# pcbcsmd.net
KiCad netlist of a schematic drawn in EAGLE
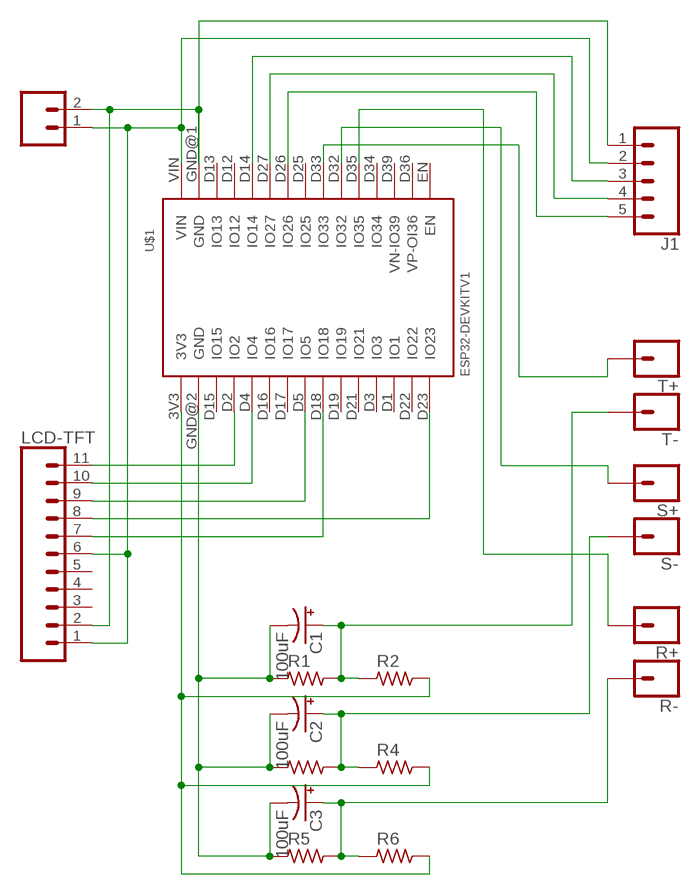
[diagram p0: schematic, sheet 1]

(export (version "E")
  (design (tool "Eeschema 10.0.6"))
  (components
    (comp (ref "C1")
      (value "100uF")
      (footprint "eagle-import:PANASONIC_D")
      (libsource (lib "eagle-import") (part "100UF-POLAR-25V-20%(ELEC)"))
    )
    (comp (ref "C2")
      (value "100uF")
      (footprint "eagle-import:PANASONIC_D")
      (libsource (lib "eagle-import") (part "100UF-POLAR-25V-20%(ELEC)"))
    )
    (comp (ref "C3")
      (value "100uF")
      (footprint "eagle-import:PANASONIC_D")
      (libsource (lib "eagle-import") (part "100UF-POLAR-25V-20%(ELEC)"))
    )
    (comp (ref "J1")
      (value "CONN_05")
      (footprint "eagle-import:1X05")
      (libsource (lib "eagle-import") (part "CONN_05"))
    )
    (comp (ref "LCD-TFT")
      (value "CONN_11")
      (footprint "eagle-import:1X11")
      (libsource (lib "eagle-import") (part "CONN_11"))
    )
    (comp (ref "POWER")
      (value "CONN_02")
      (footprint "eagle-import:1X02")
      (libsource (lib "eagle-import") (part "CONN_02"))
    )
    (comp (ref "R+")
      (value "CONN_01")
      (footprint "eagle-import:1X01")
      (libsource (lib "eagle-import") (part "CONN_01"))
    )
    (comp (ref "R-")
      (value "CONN_01")
      (footprint "eagle-import:1X01")
      (libsource (lib "eagle-import") (part "CONN_01"))
    )
    (comp (ref "R1")
      (value "R_0805")
      (footprint "eagle-import:R0805")
      (libsource (lib "eagle-import") (part "R_0805"))
    )
    (comp (ref "R2")
      (value "R_0805")
      (footprint "eagle-import:R0805")
      (libsource (lib "eagle-import") (part "R_0805"))
    )
    (comp (ref "R3")
      (value "R_0805")
      (footprint "eagle-import:R0805")
      (libsource (lib "eagle-import") (part "R_0805"))
    )
    (comp (ref "R4")
      (value "R_0805")
      (footprint "eagle-import:R0805")
      (libsource (lib "eagle-import") (part "R_0805"))
    )
    (comp (ref "R5")
      (value "R_0805")
      (footprint "eagle-import:R0805")
      (libsource (lib "eagle-import") (part "R_0805"))
    )
    (comp (ref "R6")
      (value "R_0805")
      (footprint "eagle-import:R0805")
      (libsource (lib "eagle-import") (part "R_0805"))
    )
    (comp (ref "S+")
      (value "CONN_01")
      (footprint "eagle-import:1X01")
      (libsource (lib "eagle-import") (part "CONN_01"))
    )
    (comp (ref "S-")
      (value "CONN_01")
      (footprint "eagle-import:1X01")
      (libsource (lib "eagle-import") (part "CONN_01"))
    )
    (comp (ref "T+")
      (value "CONN_01")
      (footprint "eagle-import:1X01")
      (libsource (lib "eagle-import") (part "CONN_01"))
    )
    (comp (ref "T-")
      (value "CONN_01")
      (footprint "eagle-import:1X01")
      (libsource (lib "eagle-import") (part "CONN_01"))
    )
    (comp (ref "U$1")
      (value "ESP32DEVKITV1")
      (footprint "eagle-import:ESP32-DEVKITV1")
      (libsource (lib "eagle-import") (part "ESP32DEVKITV1"))
    )
  )
  (nets
    (net (code "1") (name "Net-(C1-Pad+)") (class "Default")
      (node (ref "C1") (pin "+") (pinfunction "+_+") (pintype "passive"))
      (node (ref "R1") (pin "2") (pinfunction "2_2") (pintype "passive"))
      (node (ref "R2") (pin "1") (pinfunction "1_1") (pintype "passive"))
      (node (ref "T-") (pin "1") (pinfunction "1_1") (pintype "passive"))
    )
    (net (code "2") (name "Net-(C1-Pad-)") (class "Default")
      (node (ref "C1") (pin "-") (pinfunction "-_-") (pintype "passive"))
      (node (ref "C2") (pin "-") (pinfunction "-_-") (pintype "passive"))
      (node (ref "C3") (pin "-") (pinfunction "-_-") (pintype "passive"))
      (node (ref "R1") (pin "1") (pinfunction "1_1") (pintype "passive"))
      (node (ref "R3") (pin "1") (pinfunction "1_1") (pintype "passive"))
      (node (ref "R5") (pin "1") (pinfunction "1_1") (pintype "passive"))
      (node (ref "U$1") (pin "GND@2") (pinfunction "GND_GND@2") (pintype "bidirectional"))
    )
    (net (code "3") (name "Net-(C2-Pad+)") (class "Default")
      (node (ref "C2") (pin "+") (pinfunction "+_+") (pintype "passive"))
      (node (ref "R3") (pin "2") (pinfunction "2_2") (pintype "passive"))
      (node (ref "R4") (pin "1") (pinfunction "1_1") (pintype "passive"))
      (node (ref "S-") (pin "1") (pinfunction "1_1") (pintype "passive"))
    )
    (net (code "4") (name "Net-(C3-Pad+)") (class "Default")
      (node (ref "C3") (pin "+") (pinfunction "+_+") (pintype "passive"))
      (node (ref "R-") (pin "1") (pinfunction "1_1") (pintype "passive"))
      (node (ref "R5") (pin "2") (pinfunction "2_2") (pintype "passive"))
      (node (ref "R6") (pin "1") (pinfunction "1_1") (pintype "passive"))
    )
    (net (code "5") (name "Net-(J1-Pad1)") (class "Default")
      (node (ref "J1") (pin "1") (pinfunction "1_1") (pintype "passive"))
      (node (ref "LCD-TFT") (pin "2") (pinfunction "2_2") (pintype "passive"))
      (node (ref "POWER") (pin "2") (pinfunction "2_2") (pintype "passive"))
      (node (ref "U$1") (pin "GND@1") (pinfunction "GND_GND@1") (pintype "bidirectional"))
    )
    (net (code "6") (name "Net-(J1-Pad2)") (class "Default")
      (node (ref "J1") (pin "2") (pinfunction "2_2") (pintype "passive"))
      (node (ref "LCD-TFT") (pin "1") (pinfunction "1_1") (pintype "passive"))
      (node (ref "LCD-TFT") (pin "6") (pinfunction "6_6") (pintype "passive"))
      (node (ref "POWER") (pin "1") (pinfunction "1_1") (pintype "passive"))
      (node (ref "U$1") (pin "VIN") (pinfunction "VIN_VIN") (pintype "bidirectional"))
    )
    (net (code "7") (name "Net-(R2-Pad2)") (class "Default")
      (node (ref "R2") (pin "2") (pinfunction "2_2") (pintype "passive"))
      (node (ref "R4") (pin "2") (pinfunction "2_2") (pintype "passive"))
      (node (ref "R6") (pin "2") (pinfunction "2_2") (pintype "passive"))
      (node (ref "U$1") (pin "3V3") (pinfunction "3V3_3V3") (pintype "bidirectional"))
    )
    (net (code "8") (name "Net-(U$1-IO2)") (class "Default")
      (node (ref "LCD-TFT") (pin "11") (pinfunction "11_11") (pintype "passive"))
      (node (ref "U$1") (pin "D2") (pinfunction "IO2_D2") (pintype "bidirectional"))
    )
    (net (code "9") (name "Net-(U$1-IO4)") (class "Default")
      (node (ref "LCD-TFT") (pin "10") (pinfunction "10_10") (pintype "passive"))
      (node (ref "U$1") (pin "D4") (pinfunction "IO4_D4") (pintype "bidirectional"))
    )
    (net (code "10") (name "Net-(U$1-IO5)") (class "Default")
      (node (ref "LCD-TFT") (pin "9") (pinfunction "9_9") (pintype "passive"))
      (node (ref "U$1") (pin "D5") (pinfunction "IO5_D5") (pintype "bidirectional"))
    )
    (net (code "11") (name "Net-(U$1-IO14)") (class "Default")
      (node (ref "J1") (pin "3") (pinfunction "3_3") (pintype "passive"))
      (node (ref "U$1") (pin "D14") (pinfunction "IO14_D14") (pintype "bidirectional"))
    )
    (net (code "12") (name "Net-(U$1-IO18)") (class "Default")
      (node (ref "LCD-TFT") (pin "7") (pinfunction "7_7") (pintype "passive"))
      (node (ref "U$1") (pin "D18") (pinfunction "IO18_D18") (pintype "bidirectional"))
    )
    (net (code "13") (name "Net-(U$1-IO23)") (class "Default")
      (node (ref "LCD-TFT") (pin "8") (pinfunction "8_8") (pintype "passive"))
      (node (ref "U$1") (pin "D23") (pinfunction "IO23_D23") (pintype "bidirectional"))
    )
    (net (code "14") (name "Net-(U$1-IO26)") (class "Default")
      (node (ref "J1") (pin "5") (pinfunction "5_5") (pintype "passive"))
      (node (ref "U$1") (pin "D26") (pinfunction "IO26_D26") (pintype "bidirectional"))
    )
    (net (code "15") (name "Net-(U$1-IO27)") (class "Default")
      (node (ref "J1") (pin "4") (pinfunction "4_4") (pintype "passive"))
      (node (ref "U$1") (pin "D27") (pinfunction "IO27_D27") (pintype "bidirectional"))
    )
    (net (code "16") (name "Net-(U$1-IO32)") (class "Default")
      (node (ref "S+") (pin "1") (pinfunction "1_1") (pintype "passive"))
      (node (ref "U$1") (pin "D32") (pinfunction "IO32_D32") (pintype "bidirectional"))
    )
    (net (code "17") (name "Net-(U$1-IO33)") (class "Default")
      (node (ref "T+") (pin "1") (pinfunction "1_1") (pintype "passive"))
      (node (ref "U$1") (pin "D33") (pinfunction "IO33_D33") (pintype "bidirectional"))
    )
    (net (code "18") (name "Net-(U$1-IO35)") (class "Default")
      (node (ref "R+") (pin "1") (pinfunction "1_1") (pintype "passive"))
      (node (ref "U$1") (pin "D35") (pinfunction "IO35_D35") (pintype "bidirectional"))
    )
    (net (code "19") (name "unconnected-(LCD-TFT-Pad3)") (class "Default")
      (node (ref "LCD-TFT") (pin "3") (pinfunction "3_3") (pintype "passive"))
    )
    (net (code "20") (name "unconnected-(LCD-TFT-Pad4)") (class "Default")
      (node (ref "LCD-TFT") (pin "4") (pinfunction "4_4") (pintype "passive"))
    )
    (net (code "21") (name "unconnected-(LCD-TFT-Pad5)") (class "Default")
      (node (ref "LCD-TFT") (pin "5") (pinfunction "5_5") (pintype "passive"))
    )
    (net (code "22") (name "unconnected-(U$1-IO1-PadD1)") (class "Default")
      (node (ref "U$1") (pin "D1") (pinfunction "IO1_D1") (pintype "bidirectional"))
    )
    (net (code "23") (name "unconnected-(U$1-IO3-PadD3)") (class "Default")
      (node (ref "U$1") (pin "D3") (pinfunction "IO3_D3") (pintype "bidirectional"))
    )
    (net (code "24") (name "unconnected-(U$1-IO12-PadD12)") (class "Default")
      (node (ref "U$1") (pin "D12") (pinfunction "IO12_D12") (pintype "bidirectional"))
    )
    (net (code "25") (name "unconnected-(U$1-IO13-PadD13)") (class "Default")
      (node (ref "U$1") (pin "D13") (pinfunction "IO13_D13") (pintype "bidirectional"))
    )
    (net (code "26") (name "unconnected-(U$1-IO15-PadD15)") (class "Default")
      (node (ref "U$1") (pin "D15") (pinfunction "IO15_D15") (pintype "bidirectional"))
    )
    (net (code "27") (name "unconnected-(U$1-IO16-PadD16)") (class "Default")
      (node (ref "U$1") (pin "D16") (pinfunction "IO16_D16") (pintype "bidirectional"))
    )
    (net (code "28") (name "unconnected-(U$1-IO17-PadD17)") (class "Default")
      (node (ref "U$1") (pin "D17") (pinfunction "IO17_D17") (pintype "bidirectional"))
    )
    (net (code "29") (name "unconnected-(U$1-IO19-PadD19)") (class "Default")
      (node (ref "U$1") (pin "D19") (pinfunction "IO19_D19") (pintype "bidirectional"))
    )
    (net (code "30") (name "unconnected-(U$1-IO21-PadD21)") (class "Default")
      (node (ref "U$1") (pin "D21") (pinfunction "IO21_D21") (pintype "bidirectional"))
    )
    (net (code "31") (name "unconnected-(U$1-IO22-PadD22)") (class "Default")
      (node (ref "U$1") (pin "D22") (pinfunction "IO22_D22") (pintype "bidirectional"))
    )
    (net (code "32") (name "unconnected-(U$1-IO25-PadD25)") (class "Default")
      (node (ref "U$1") (pin "D25") (pinfunction "IO25_D25") (pintype "bidirectional"))
    )
    (net (code "33") (name "unconnected-(U$1-IO34-PadD34)") (class "Default")
      (node (ref "U$1") (pin "D34") (pinfunction "IO34_D34") (pintype "bidirectional"))
    )
    (net (code "34") (name "unconnected-(U$1-PadEN)") (class "Default")
      (node (ref "U$1") (pin "EN") (pinfunction "EN_EN") (pintype "bidirectional"))
    )
    (net (code "35") (name "unconnected-(U$1-VN-IO39-PadD39)") (class "Default")
      (node (ref "U$1") (pin "D39") (pinfunction "VN-IO39_D39") (pintype "bidirectional"))
    )
    (net (code "36") (name "unconnected-(U$1-VP-OI36-PadD36)") (class "Default")
      (node (ref "U$1") (pin "D36") (pinfunction "VP-OI36_D36") (pintype "bidirectional"))
    )
  )
)
